# joulia_controller.net
KiCad netlist of a schematic drawn in EAGLE
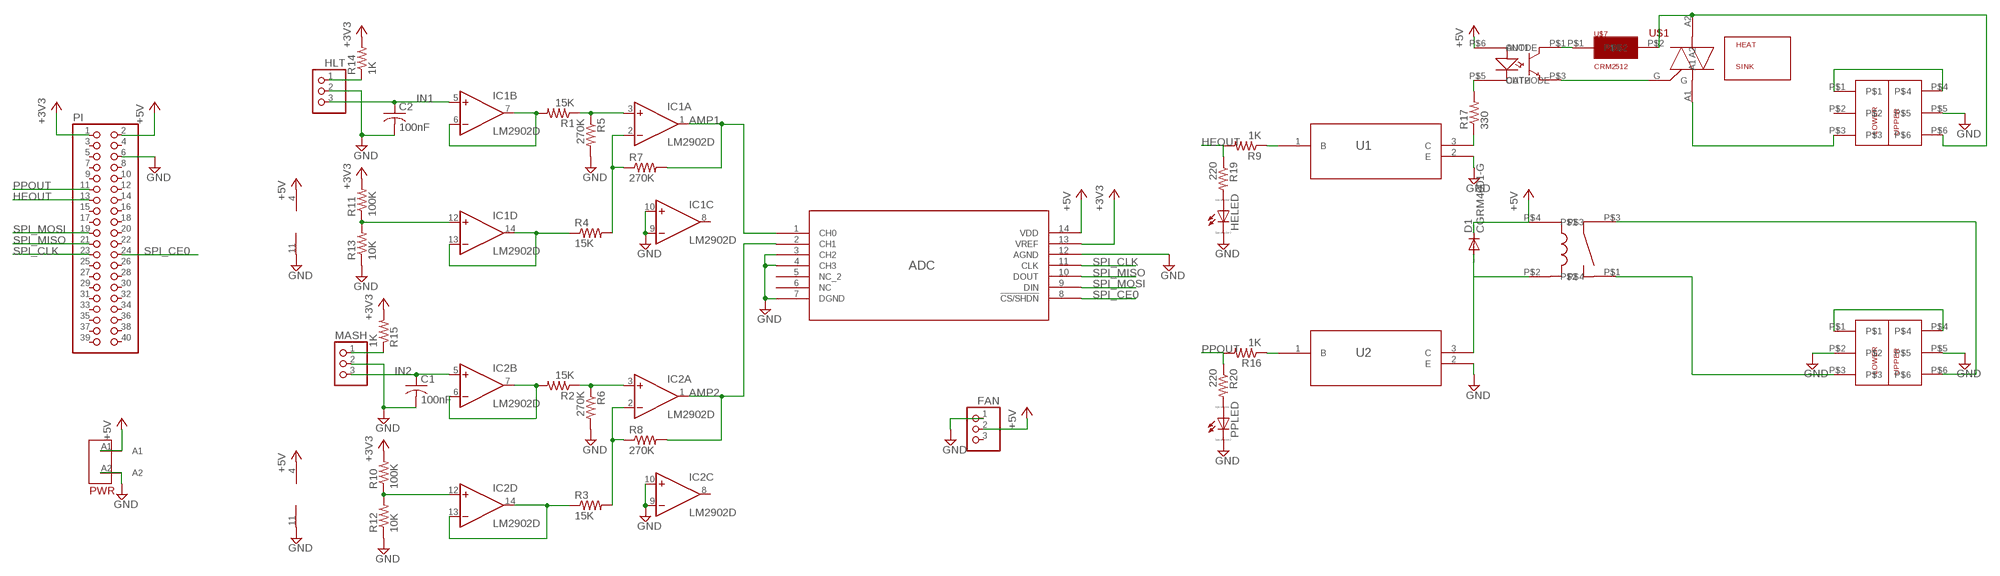
[diagram p0: schematic, sheet 1]

(export (version "E")
  (design (tool "Eeschema 10.0.6"))
  (components
    (comp (ref "ADC")
      (value "MCP3004-I/SL")
      (footprint "eagle-import:SOIC14-N_MC")
      (fields (field (name "MANUFACTURER_PART_NUMBER") "MCP3004ISL"))
      (libsource (lib "eagle-import") (part "MCP3004-I/SL"))
    )
    (comp (ref "C1")
      (value "100nF")
      (footprint "eagle-import:C0402")
      (libsource (lib "eagle-import") (part "C-USC0402"))
    )
    (comp (ref "C2")
      (value "100nF")
      (footprint "eagle-import:C0402")
      (libsource (lib "eagle-import") (part "C-USC0402"))
    )
    (comp (ref "D1")
      (value "CGRM4001-G")
      (footprint "eagle-import:SOD-123_MINI-SMA")
      (libsource (lib "eagle-import") (part "CGRM400-G1"))
    )
    (comp (ref "FAN")
      (value "PINHD-1X3")
      (footprint "eagle-import:1X03")
      (libsource (lib "eagle-import") (part "PINHD-1X3"))
    )
    (comp (ref "HELED")
      (value "LED_ESML0603")
      (footprint "eagle-import:LED_SML0603")
      (libsource (lib "eagle-import") (part "LED_ESML0603"))
    )
    (comp (ref "HLT")
      (value "PINHD-1X3")
      (footprint "eagle-import:1X03")
      (libsource (lib "eagle-import") (part "PINHD-1X3"))
    )
    (comp (ref "IC1")
      (value "LM2902D")
      (footprint "eagle-import:SO14")
      (libsource (lib "eagle-import") (part "LM2902D"))
    )
    (comp (ref "IC2")
      (value "LM2902D")
      (footprint "eagle-import:SO14")
      (libsource (lib "eagle-import") (part "LM2902D"))
    )
    (comp (ref "MASH")
      (value "PINHD-1X3")
      (footprint "eagle-import:1X03")
      (libsource (lib "eagle-import") (part "PINHD-1X3"))
    )
    (comp (ref "PI")
      (value "PINHD-2X20")
      (footprint "eagle-import:2X20")
      (libsource (lib "eagle-import") (part "PINHD-2X20"))
    )
    (comp (ref "PPLED")
      (value "LED_ESML0603")
      (footprint "eagle-import:LED_SML0603")
      (libsource (lib "eagle-import") (part "LED_ESML0603"))
    )
    (comp (ref "PWR")
      (value "MTA-100-2HDR2")
      (footprint "eagle-import:HDR2")
      (libsource (lib "eagle-import") (part "MTA-100-2HDR2"))
    )
    (comp (ref "R1")
      (value "15K")
      (footprint "eagle-import:R0402")
      (libsource (lib "eagle-import") (part "R-US_R0402"))
    )
    (comp (ref "R2")
      (value "15K")
      (footprint "eagle-import:R0402")
      (libsource (lib "eagle-import") (part "R-US_R0402"))
    )
    (comp (ref "R3")
      (value "15K")
      (footprint "eagle-import:R0402")
      (libsource (lib "eagle-import") (part "R-US_R0402"))
    )
    (comp (ref "R4")
      (value "15K")
      (footprint "eagle-import:R0402")
      (libsource (lib "eagle-import") (part "R-US_R0402"))
    )
    (comp (ref "R5")
      (value "270K")
      (footprint "eagle-import:R0402")
      (libsource (lib "eagle-import") (part "R-US_R0402"))
    )
    (comp (ref "R6")
      (value "270K")
      (footprint "eagle-import:R0402")
      (libsource (lib "eagle-import") (part "R-US_R0402"))
    )
    (comp (ref "R7")
      (value "270K")
      (footprint "eagle-import:R0402")
      (libsource (lib "eagle-import") (part "R-US_R0402"))
    )
    (comp (ref "R8")
      (value "270K")
      (footprint "eagle-import:R0402")
      (libsource (lib "eagle-import") (part "R-US_R0402"))
    )
    (comp (ref "R9")
      (value "1K")
      (footprint "eagle-import:R0402")
      (libsource (lib "eagle-import") (part "resistor_348_R-US_R0402"))
    )
    (comp (ref "R10")
      (value "100K")
      (footprint "eagle-import:R0402")
      (libsource (lib "eagle-import") (part "R-US_R0402"))
    )
    (comp (ref "R11")
      (value "100K")
      (footprint "eagle-import:R0402")
      (libsource (lib "eagle-import") (part "R-US_R0402"))
    )
    (comp (ref "R12")
      (value "10K")
      (footprint "eagle-import:R0402")
      (libsource (lib "eagle-import") (part "resistor_348_R-US_R0402"))
    )
    (comp (ref "R13")
      (value "10K")
      (footprint "eagle-import:R0402")
      (libsource (lib "eagle-import") (part "resistor_348_R-US_R0402"))
    )
    (comp (ref "R14")
      (value "1K")
      (footprint "eagle-import:R0402")
      (libsource (lib "eagle-import") (part "resistor_348_R-US_R0402"))
    )
    (comp (ref "R15")
      (value "1K")
      (footprint "eagle-import:R0402")
      (libsource (lib "eagle-import") (part "resistor_348_R-US_R0402"))
    )
    (comp (ref "R16")
      (value "1K")
      (footprint "eagle-import:R0402")
      (libsource (lib "eagle-import") (part "resistor_348_R-US_R0402"))
    )
    (comp (ref "R17")
      (value "330")
      (footprint "eagle-import:R1206")
      (libsource (lib "eagle-import") (part "resistor_348_R-US_R1206"))
    )
    (comp (ref "R19")
      (value "220")
      (footprint "eagle-import:R0402")
      (libsource (lib "eagle-import") (part "R-US_R0402"))
    )
    (comp (ref "R20")
      (value "220")
      (footprint "eagle-import:R0402")
      (libsource (lib "eagle-import") (part "R-US_R0402"))
    )
    (comp (ref "U$1")
      (value "T3050H-6I")
      (footprint "eagle-import:TO-220")
      (libsource (lib "eagle-import") (part "T3050H-6I"))
    )
    (comp (ref "U$2")
      (value "VM1-038-1AEHORIZONTAL")
      (footprint "eagle-import:VM2-038-1AE")
      (libsource (lib "eagle-import") (part "VM1-038-1AEHORIZONTAL"))
    )
    (comp (ref "U$3")
      (value "G5LE-1A4_DC5")
      (footprint "eagle-import:G5LE-1A4_DC5")
      (libsource (lib "eagle-import") (part "G5LE-1A4_DC5"))
    )
    (comp (ref "U$4")
      (value "PC1725041")
      (footprint "eagle-import:PC-MKKDS1.5_3-5.08")
      (libsource (lib "eagle-import") (part "PC1725041"))
    )
    (comp (ref "U$5")
      (value "MOC3020S")
      (footprint "eagle-import:6-SMD")
      (libsource (lib "eagle-import") (part "MOC3020S"))
    )
    (comp (ref "U$6")
      (value "PC1719028")
      (footprint "eagle-import:PC-MKKDS5_3-9.5")
      (libsource (lib "eagle-import") (part "PC1719028"))
    )
    (comp (ref "U$7")
      (value "CRM2512")
      (footprint "eagle-import:2512(6432METRIC)")
      (libsource (lib "eagle-import") (part "CRM2512"))
    )
    (comp (ref "U1")
      (value "MMBT2222ALT1G")
      (footprint "eagle-import:SOT-23")
      (libsource (lib "eagle-import") (part "MMBT2222ALT1G"))
    )
    (comp (ref "U2")
      (value "MMBT2222ALT1G")
      (footprint "eagle-import:SOT-23")
      (libsource (lib "eagle-import") (part "MMBT2222ALT1G"))
    )
  )
  (nets
    (net (code "1") (name "+3V3") (class "Default")
      (node (ref "ADC") (pin "13") (pinfunction "VREF_13") (pintype "input"))
      (node (ref "PI") (pin "1") (pinfunction "1_1") (pintype "passive"))
      (node (ref "R10") (pin "2") (pinfunction "2_2") (pintype "passive"))
      (node (ref "R11") (pin "2") (pinfunction "2_2") (pintype "passive"))
      (node (ref "R14") (pin "2") (pinfunction "2_2") (pintype "passive"))
      (node (ref "R15") (pin "2") (pinfunction "2_2") (pintype "passive"))
    )
    (net (code "2") (name "+5V") (class "Default")
      (node (ref "ADC") (pin "14") (pinfunction "VDD_14") (pintype "passive"))
      (node (ref "D1") (pin "C") (pinfunction "C_C") (pintype "passive"))
      (node (ref "FAN") (pin "2") (pinfunction "2_2") (pintype "passive"))
      (node (ref "IC1") (pin "4") (pinfunction "V+_4") (pintype "power_in"))
      (node (ref "IC2") (pin "4") (pinfunction "V+_4") (pintype "power_in"))
      (node (ref "PI") (pin "2") (pinfunction "2_2") (pintype "passive"))
      (node (ref "PWR") (pin "A1") (pinfunction "A1_A1") (pintype "bidirectional"))
      (node (ref "U$3") (pin "P$4") (pinfunction "P$1_P$4") (pintype "bidirectional"))
      (node (ref "U$5") (pin "P$6") (pinfunction "ANODE_P$6") (pintype "bidirectional"))
    )
    (net (code "3") (name "/AMP1") (class "Default")
      (node (ref "ADC") (pin "1") (pinfunction "CH0_1") (pintype "input"))
      (node (ref "IC1") (pin "1") (pinfunction "OUT_1") (pintype "output"))
      (node (ref "R7") (pin "2") (pinfunction "2_2") (pintype "passive"))
    )
    (net (code "4") (name "/AMP2") (class "Default")
      (node (ref "ADC") (pin "2") (pinfunction "CH1_2") (pintype "input"))
      (node (ref "IC2") (pin "1") (pinfunction "OUT_1") (pintype "output"))
      (node (ref "R8") (pin "2") (pinfunction "2_2") (pintype "passive"))
    )
    (net (code "5") (name "/HEOUT") (class "Default")
      (node (ref "PI") (pin "13") (pinfunction "13_13") (pintype "passive"))
      (node (ref "R19") (pin "1") (pinfunction "1_1") (pintype "passive"))
      (node (ref "R9") (pin "2") (pinfunction "2_2") (pintype "passive"))
    )
    (net (code "6") (name "/IN1") (class "Default")
      (node (ref "C2") (pin "1") (pinfunction "1_1") (pintype "passive"))
      (node (ref "HLT") (pin "3") (pinfunction "3_3") (pintype "passive"))
      (node (ref "IC1") (pin "5") (pinfunction "+IN_5") (pintype "input"))
    )
    (net (code "7") (name "/IN2") (class "Default")
      (node (ref "C1") (pin "1") (pinfunction "1_1") (pintype "passive"))
      (node (ref "IC2") (pin "5") (pinfunction "+IN_5") (pintype "input"))
      (node (ref "MASH") (pin "3") (pinfunction "3_3") (pintype "passive"))
    )
    (net (code "8") (name "/PPOUT") (class "Default")
      (node (ref "PI") (pin "11") (pinfunction "11_11") (pintype "passive"))
      (node (ref "R16") (pin "2") (pinfunction "2_2") (pintype "passive"))
      (node (ref "R20") (pin "1") (pinfunction "1_1") (pintype "passive"))
    )
    (net (code "9") (name "/SPI_CE0") (class "Default")
      (node (ref "ADC") (pin "8") (pinfunction "~{CS/SHDN}_8") (pintype "input"))
      (node (ref "PI") (pin "24") (pinfunction "24_24") (pintype "passive"))
    )
    (net (code "10") (name "/SPI_CLK") (class "Default")
      (node (ref "ADC") (pin "11") (pinfunction "CLK_11") (pintype "input"))
      (node (ref "PI") (pin "23") (pinfunction "23_23") (pintype "passive"))
    )
    (net (code "11") (name "/SPI_MISO") (class "Default")
      (node (ref "ADC") (pin "10") (pinfunction "DOUT_10") (pintype "output"))
      (node (ref "PI") (pin "21") (pinfunction "21_21") (pintype "passive"))
    )
    (net (code "12") (name "/SPI_MOSI") (class "Default")
      (node (ref "ADC") (pin "9") (pinfunction "DIN_9") (pintype "input"))
      (node (ref "PI") (pin "19") (pinfunction "19_19") (pintype "passive"))
    )
    (net (code "13") (name "GND") (class "Default")
      (node (ref "ADC") (pin "12") (pinfunction "AGND_12") (pintype "passive"))
      (node (ref "ADC") (pin "3") (pinfunction "CH2_3") (pintype "input"))
      (node (ref "ADC") (pin "4") (pinfunction "CH3_4") (pintype "input"))
      (node (ref "ADC") (pin "7") (pinfunction "DGND_7") (pintype "passive"))
      (node (ref "C1") (pin "2") (pinfunction "2_2") (pintype "passive"))
      (node (ref "C2") (pin "2") (pinfunction "2_2") (pintype "passive"))
      (node (ref "FAN") (pin "1") (pinfunction "1_1") (pintype "passive"))
      (node (ref "HELED") (pin "C") (pinfunction "C_C") (pintype "passive"))
      (node (ref "HLT") (pin "2") (pinfunction "2_2") (pintype "passive"))
      (node (ref "IC1") (pin "10") (pinfunction "+IN_10") (pintype "input"))
      (node (ref "IC1") (pin "11") (pinfunction "V-_11") (pintype "power_in"))
      (node (ref "IC1") (pin "9") (pinfunction "-IN_9") (pintype "input"))
      (node (ref "IC2") (pin "10") (pinfunction "+IN_10") (pintype "input"))
      (node (ref "IC2") (pin "11") (pinfunction "V-_11") (pintype "power_in"))
      (node (ref "IC2") (pin "9") (pinfunction "-IN_9") (pintype "input"))
      (node (ref "MASH") (pin "2") (pinfunction "2_2") (pintype "passive"))
      (node (ref "PI") (pin "6") (pinfunction "6_6") (pintype "passive"))
      (node (ref "PPLED") (pin "C") (pinfunction "C_C") (pintype "passive"))
      (node (ref "PWR") (pin "A2") (pinfunction "A2_A2") (pintype "bidirectional"))
      (node (ref "R12") (pin "1") (pinfunction "1_1") (pintype "passive"))
      (node (ref "R13") (pin "1") (pinfunction "1_1") (pintype "passive"))
      (node (ref "R5") (pin "2") (pinfunction "2_2") (pintype "passive"))
      (node (ref "R6") (pin "2") (pinfunction "2_2") (pintype "passive"))
      (node (ref "U$4") (pin "P$2") (pinfunction "P$2_P$2") (pintype "bidirectional"))
      (node (ref "U$4") (pin "P$5") (pinfunction "P$5_P$5") (pintype "bidirectional"))
      (node (ref "U$6") (pin "P$5") (pinfunction "P$5_P$5") (pintype "bidirectional"))
      (node (ref "U1") (pin "2") (pinfunction "E_2") (pintype "passive"))
      (node (ref "U2") (pin "2") (pinfunction "E_2") (pintype "passive"))
    )
    (net (code "14") (name "Net-(HELED-PadA)") (class "Default")
      (node (ref "HELED") (pin "A") (pinfunction "A_A") (pintype "passive"))
      (node (ref "R19") (pin "2") (pinfunction "2_2") (pintype "passive"))
    )
    (net (code "15") (name "Net-(HLT-Pad1)") (class "Default")
      (node (ref "HLT") (pin "1") (pinfunction "1_1") (pintype "passive"))
      (node (ref "R14") (pin "1") (pinfunction "1_1") (pintype "passive"))
    )
    (net (code "16") (name "Net-(IC1A-+IN)") (class "Default")
      (node (ref "IC1") (pin "3") (pinfunction "+IN_3") (pintype "input"))
      (node (ref "R1") (pin "1") (pinfunction "1_1") (pintype "passive"))
      (node (ref "R5") (pin "1") (pinfunction "1_1") (pintype "passive"))
    )
    (net (code "17") (name "Net-(IC1A--IN)") (class "Default")
      (node (ref "IC1") (pin "2") (pinfunction "-IN_2") (pintype "input"))
      (node (ref "R4") (pin "2") (pinfunction "2_2") (pintype "passive"))
      (node (ref "R7") (pin "1") (pinfunction "1_1") (pintype "passive"))
    )
    (net (code "18") (name "Net-(IC1B--IN)") (class "Default")
      (node (ref "IC1") (pin "6") (pinfunction "-IN_6") (pintype "input"))
      (node (ref "IC1") (pin "7") (pinfunction "OUT_7") (pintype "output"))
      (node (ref "R1") (pin "2") (pinfunction "2_2") (pintype "passive"))
    )
    (net (code "19") (name "Net-(IC1D-+IN)") (class "Default")
      (node (ref "IC1") (pin "12") (pinfunction "+IN_12") (pintype "input"))
      (node (ref "R11") (pin "1") (pinfunction "1_1") (pintype "passive"))
      (node (ref "R13") (pin "2") (pinfunction "2_2") (pintype "passive"))
    )
    (net (code "20") (name "Net-(IC1D--IN)") (class "Default")
      (node (ref "IC1") (pin "13") (pinfunction "-IN_13") (pintype "input"))
      (node (ref "IC1") (pin "14") (pinfunction "OUT_14") (pintype "output"))
      (node (ref "R4") (pin "1") (pinfunction "1_1") (pintype "passive"))
    )
    (net (code "21") (name "Net-(IC2A-+IN)") (class "Default")
      (node (ref "IC2") (pin "3") (pinfunction "+IN_3") (pintype "input"))
      (node (ref "R2") (pin "1") (pinfunction "1_1") (pintype "passive"))
      (node (ref "R6") (pin "1") (pinfunction "1_1") (pintype "passive"))
    )
    (net (code "22") (name "Net-(IC2A--IN)") (class "Default")
      (node (ref "IC2") (pin "2") (pinfunction "-IN_2") (pintype "input"))
      (node (ref "R3") (pin "2") (pinfunction "2_2") (pintype "passive"))
      (node (ref "R8") (pin "1") (pinfunction "1_1") (pintype "passive"))
    )
    (net (code "23") (name "Net-(IC2B--IN)") (class "Default")
      (node (ref "IC2") (pin "6") (pinfunction "-IN_6") (pintype "input"))
      (node (ref "IC2") (pin "7") (pinfunction "OUT_7") (pintype "output"))
      (node (ref "R2") (pin "2") (pinfunction "2_2") (pintype "passive"))
    )
    (net (code "24") (name "Net-(IC2D-+IN)") (class "Default")
      (node (ref "IC2") (pin "12") (pinfunction "+IN_12") (pintype "input"))
      (node (ref "R10") (pin "1") (pinfunction "1_1") (pintype "passive"))
      (node (ref "R12") (pin "2") (pinfunction "2_2") (pintype "passive"))
    )
    (net (code "25") (name "Net-(IC2D--IN)") (class "Default")
      (node (ref "IC2") (pin "13") (pinfunction "-IN_13") (pintype "input"))
      (node (ref "IC2") (pin "14") (pinfunction "OUT_14") (pintype "output"))
      (node (ref "R3") (pin "1") (pinfunction "1_1") (pintype "passive"))
    )
    (net (code "26") (name "Net-(MASH-Pad1)") (class "Default")
      (node (ref "MASH") (pin "1") (pinfunction "1_1") (pintype "passive"))
      (node (ref "R15") (pin "1") (pinfunction "1_1") (pintype "passive"))
    )
    (net (code "27") (name "Net-(PPLED-PadA)") (class "Default")
      (node (ref "PPLED") (pin "A") (pinfunction "A_A") (pintype "passive"))
      (node (ref "R20") (pin "2") (pinfunction "2_2") (pintype "passive"))
    )
    (net (code "28") (name "Net-(U$1-PadA1)") (class "Default")
      (node (ref "U$1") (pin "A1") (pinfunction "A1_A1") (pintype "bidirectional"))
      (node (ref "U$6") (pin "P$3") (pinfunction "P$3_P$3") (pintype "bidirectional"))
    )
    (net (code "29") (name "Net-(U$1-PadA2)") (class "Default")
      (node (ref "U$1") (pin "A2") (pinfunction "A2_A2") (pintype "bidirectional"))
      (node (ref "U$6") (pin "P$6") (pinfunction "P$6_P$6") (pintype "bidirectional"))
      (node (ref "U$7") (pin "P$2") (pinfunction "P$2_P$2") (pintype "bidirectional"))
    )
    (net (code "30") (name "Net-(U$3-P$4)") (class "Default")
      (node (ref "U$3") (pin "P$1") (pinfunction "P$4_P$1") (pintype "bidirectional"))
      (node (ref "U$4") (pin "P$3") (pinfunction "P$3_P$3") (pintype "bidirectional"))
    )
    (net (code "31") (name "Net-(U$3-PadP$3)") (class "Default")
      (node (ref "U$3") (pin "P$3") (pinfunction "P$3_P$3") (pintype "bidirectional"))
      (node (ref "U$4") (pin "P$6") (pinfunction "P$6_P$6") (pintype "bidirectional"))
    )
    (net (code "32") (name "Net-(U$4-PadP$1)") (class "Default")
      (node (ref "U$4") (pin "P$1") (pinfunction "P$1_P$1") (pintype "bidirectional"))
      (node (ref "U$4") (pin "P$4") (pinfunction "P$4_P$4") (pintype "bidirectional"))
    )
    (net (code "33") (name "Net-(U$5-CATHODE)") (class "Default")
      (node (ref "R17") (pin "2") (pinfunction "2_2") (pintype "passive"))
      (node (ref "U$5") (pin "P$5") (pinfunction "CATHODE_P$5") (pintype "bidirectional"))
    )
    (net (code "34") (name "Net-(U$5-OUT1)") (class "Default")
      (node (ref "U$5") (pin "P$1") (pinfunction "OUT1_P$1") (pintype "bidirectional"))
      (node (ref "U$7") (pin "P$1") (pinfunction "P$1_P$1") (pintype "bidirectional"))
    )
    (net (code "35") (name "Net-(U$5-OUT2)") (class "Default")
      (node (ref "U$1") (pin "G") (pinfunction "G_G") (pintype "bidirectional"))
      (node (ref "U$5") (pin "P$3") (pinfunction "OUT2_P$3") (pintype "bidirectional"))
    )
    (net (code "36") (name "Net-(U$6-PadP$1)") (class "Default")
      (node (ref "U$6") (pin "P$1") (pinfunction "P$1_P$1") (pintype "bidirectional"))
      (node (ref "U$6") (pin "P$4") (pinfunction "P$4_P$4") (pintype "bidirectional"))
    )
    (net (code "37") (name "Net-(U1-B)") (class "Default")
      (node (ref "R9") (pin "1") (pinfunction "1_1") (pintype "passive"))
      (node (ref "U1") (pin "1") (pinfunction "B_1") (pintype "passive"))
    )
    (net (code "38") (name "Net-(U1-C)") (class "Default")
      (node (ref "R17") (pin "1") (pinfunction "1_1") (pintype "passive"))
      (node (ref "U1") (pin "3") (pinfunction "C_3") (pintype "passive"))
    )
    (net (code "39") (name "Net-(U2-B)") (class "Default")
      (node (ref "R16") (pin "1") (pinfunction "1_1") (pintype "passive"))
      (node (ref "U2") (pin "1") (pinfunction "B_1") (pintype "passive"))
    )
    (net (code "40") (name "Net-(U2-C)") (class "Default")
      (node (ref "D1") (pin "A") (pinfunction "A_A") (pintype "passive"))
      (node (ref "U$3") (pin "P$2") (pinfunction "P$2_P$2") (pintype "bidirectional"))
      (node (ref "U2") (pin "3") (pinfunction "C_3") (pintype "passive"))
    )
    (net (code "41") (name "unconnected-(ADC-NC-Pad6)") (class "Default")
      (node (ref "ADC") (pin "6") (pinfunction "NC_6") (pintype "no_connect"))
    )
    (net (code "42") (name "unconnected-(ADC-NC_2-Pad5)") (class "Default")
      (node (ref "ADC") (pin "5") (pinfunction "NC_2_5") (pintype "no_connect"))
    )
    (net (code "43") (name "unconnected-(FAN-Pad3)") (class "Default")
      (node (ref "FAN") (pin "3") (pinfunction "3_3") (pintype "passive"))
    )
    (net (code "44") (name "unconnected-(IC1C-OUT-Pad8)") (class "Default")
      (node (ref "IC1") (pin "8") (pinfunction "OUT_8") (pintype "output"))
    )
    (net (code "45") (name "unconnected-(IC2C-OUT-Pad8)") (class "Default")
      (node (ref "IC2") (pin "8") (pinfunction "OUT_8") (pintype "output"))
    )
    (net (code "46") (name "unconnected-(PI-Pad3)") (class "Default")
      (node (ref "PI") (pin "3") (pinfunction "3_3") (pintype "passive"))
    )
    (net (code "47") (name "unconnected-(PI-Pad4)") (class "Default")
      (node (ref "PI") (pin "4") (pinfunction "4_4") (pintype "passive"))
    )
    (net (code "48") (name "unconnected-(PI-Pad5)") (class "Default")
      (node (ref "PI") (pin "5") (pinfunction "5_5") (pintype "passive"))
    )
    (net (code "49") (name "unconnected-(PI-Pad7)") (class "Default")
      (node (ref "PI") (pin "7") (pinfunction "7_7") (pintype "passive"))
    )
    (net (code "50") (name "unconnected-(PI-Pad8)") (class "Default")
      (node (ref "PI") (pin "8") (pinfunction "8_8") (pintype "passive"))
    )
    (net (code "51") (name "unconnected-(PI-Pad9)") (class "Default")
      (node (ref "PI") (pin "9") (pinfunction "9_9") (pintype "passive"))
    )
    (net (code "52") (name "unconnected-(PI-Pad10)") (class "Default")
      (node (ref "PI") (pin "10") (pinfunction "10_10") (pintype "passive"))
    )
    (net (code "53") (name "unconnected-(PI-Pad12)") (class "Default")
      (node (ref "PI") (pin "12") (pinfunction "12_12") (pintype "passive"))
    )
    (net (code "54") (name "unconnected-(PI-Pad14)") (class "Default")
      (node (ref "PI") (pin "14") (pinfunction "14_14") (pintype "passive"))
    )
    (net (code "55") (name "unconnected-(PI-Pad15)") (class "Default")
      (node (ref "PI") (pin "15") (pinfunction "15_15") (pintype "passive"))
    )
    (net (code "56") (name "unconnected-(PI-Pad16)") (class "Default")
      (node (ref "PI") (pin "16") (pinfunction "16_16") (pintype "passive"))
    )
    (net (code "57") (name "unconnected-(PI-Pad17)") (class "Default")
      (node (ref "PI") (pin "17") (pinfunction "17_17") (pintype "passive"))
    )
    (net (code "58") (name "unconnected-(PI-Pad18)") (class "Default")
      (node (ref "PI") (pin "18") (pinfunction "18_18") (pintype "passive"))
    )
    (net (code "59") (name "unconnected-(PI-Pad20)") (class "Default")
      (node (ref "PI") (pin "20") (pinfunction "20_20") (pintype "passive"))
    )
    (net (code "60") (name "unconnected-(PI-Pad22)") (class "Default")
      (node (ref "PI") (pin "22") (pinfunction "22_22") (pintype "passive"))
    )
    (net (code "61") (name "unconnected-(PI-Pad25)") (class "Default")
      (node (ref "PI") (pin "25") (pinfunction "25_25") (pintype "passive"))
    )
    (net (code "62") (name "unconnected-(PI-Pad26)") (class "Default")
      (node (ref "PI") (pin "26") (pinfunction "26_26") (pintype "passive"))
    )
    (net (code "63") (name "unconnected-(PI-Pad27)") (class "Default")
      (node (ref "PI") (pin "27") (pinfunction "27_27") (pintype "passive"))
    )
    (net (code "64") (name "unconnected-(PI-Pad28)") (class "Default")
      (node (ref "PI") (pin "28") (pinfunction "28_28") (pintype "passive"))
    )
    (net (code "65") (name "unconnected-(PI-Pad29)") (class "Default")
      (node (ref "PI") (pin "29") (pinfunction "29_29") (pintype "passive"))
    )
    (net (code "66") (name "unconnected-(PI-Pad30)") (class "Default")
      (node (ref "PI") (pin "30") (pinfunction "30_30") (pintype "passive"))
    )
    (net (code "67") (name "unconnected-(PI-Pad31)") (class "Default")
      (node (ref "PI") (pin "31") (pinfunction "31_31") (pintype "passive"))
    )
    (net (code "68") (name "unconnected-(PI-Pad32)") (class "Default")
      (node (ref "PI") (pin "32") (pinfunction "32_32") (pintype "passive"))
    )
    (net (code "69") (name "unconnected-(PI-Pad33)") (class "Default")
      (node (ref "PI") (pin "33") (pinfunction "33_33") (pintype "passive"))
    )
    (net (code "70") (name "unconnected-(PI-Pad34)") (class "Default")
      (node (ref "PI") (pin "34") (pinfunction "34_34") (pintype "passive"))
    )
    (net (code "71") (name "unconnected-(PI-Pad35)") (class "Default")
      (node (ref "PI") (pin "35") (pinfunction "35_35") (pintype "passive"))
    )
    (net (code "72") (name "unconnected-(PI-Pad36)") (class "Default")
      (node (ref "PI") (pin "36") (pinfunction "36_36") (pintype "passive"))
    )
    (net (code "73") (name "unconnected-(PI-Pad37)") (class "Default")
      (node (ref "PI") (pin "37") (pinfunction "37_37") (pintype "passive"))
    )
    (net (code "74") (name "unconnected-(PI-Pad38)") (class "Default")
      (node (ref "PI") (pin "38") (pinfunction "38_38") (pintype "passive"))
    )
    (net (code "75") (name "unconnected-(PI-Pad39)") (class "Default")
      (node (ref "PI") (pin "39") (pinfunction "39_39") (pintype "passive"))
    )
    (net (code "76") (name "unconnected-(PI-Pad40)") (class "Default")
      (node (ref "PI") (pin "40") (pinfunction "40_40") (pintype "passive"))
    )
    (net (code "77") (name "unconnected-(U$6-PadP$2)") (class "Default")
      (node (ref "U$6") (pin "P$2") (pinfunction "P$2_P$2") (pintype "bidirectional"))
    )
  )
)
